# Main.net
KiCad netlist of a schematic drawn in Altium Designer
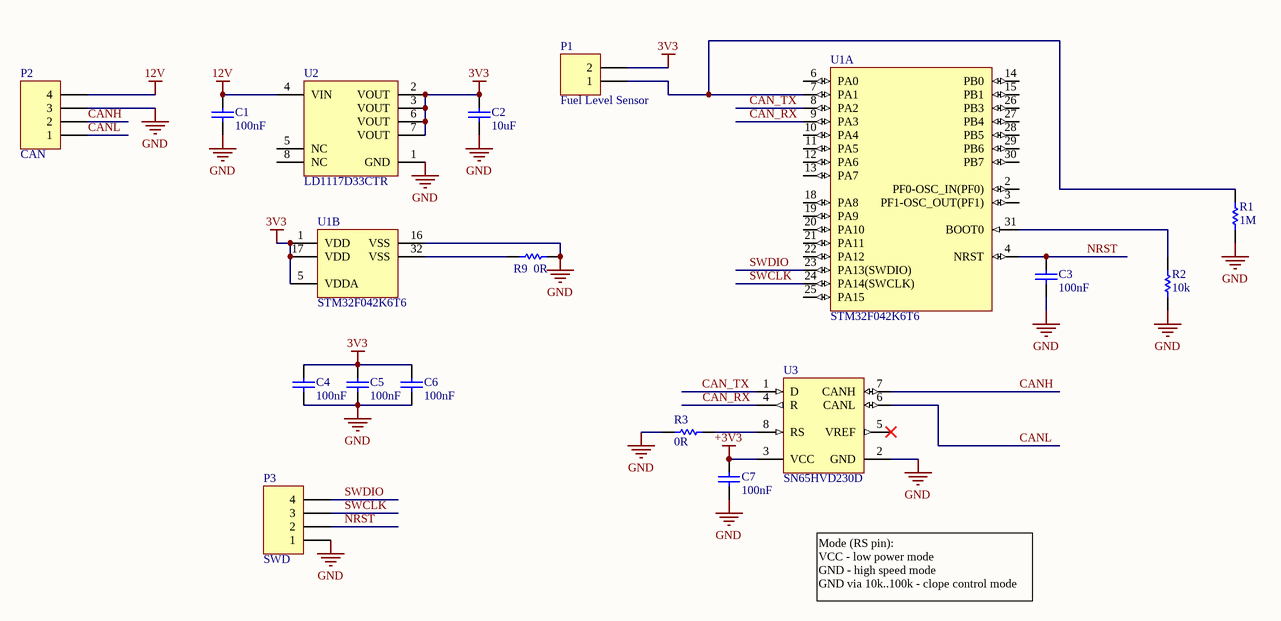
[diagram p0: Main.SchDoc]

(export (version "E")
  (design (tool "Eeschema 10.0.6"))
  (components
    (comp (ref "C1")
      (value "100nF")
      (footprint "CAP_0805_IPC_MD")
      (description "Capacitor")
      (fields (field (name "Comment") "Cap"))
      (libsource (lib "FuelLevelSensor") (part "Cap"))
    )
    (comp (ref "C2")
      (value "10uF")
      (footprint "CAP_0805_IPC_MD")
      (description "Capacitor")
      (fields (field (name "Comment") "Cap"))
      (libsource (lib "FuelLevelSensor") (part "Cap"))
    )
    (comp (ref "C3")
      (value "100nF")
      (footprint "CAP_0805_IPC_MD")
      (description "Capacitor")
      (fields (field (name "Comment") "Cap"))
      (libsource (lib "FuelLevelSensor") (part "Cap"))
    )
    (comp (ref "C4")
      (value "100nF")
      (footprint "CAP_0805_IPC_MD")
      (description "Capacitor")
      (fields (field (name "Comment") "Cap"))
      (libsource (lib "FuelLevelSensor") (part "Cap"))
    )
    (comp (ref "C5")
      (value "100nF")
      (footprint "CAP_0805_IPC_MD")
      (description "Capacitor")
      (fields (field (name "Comment") "Cap"))
      (libsource (lib "FuelLevelSensor") (part "Cap"))
    )
    (comp (ref "C6")
      (value "100nF")
      (footprint "CAP_0805_IPC_MD")
      (description "Capacitor")
      (fields (field (name "Comment") "Cap"))
      (libsource (lib "FuelLevelSensor") (part "Cap"))
    )
    (comp (ref "C7")
      (value "100nF")
      (footprint "CAP_0805_IPC_MD")
      (description "Capacitor")
      (fields (field (name "MANUFACTURER") "Samsung") (field (name "Comment") "Cap"))
      (libsource (lib "DataLogger") (part "Cap"))
    )
    (comp (ref "P1")
      (value "Fuel Level Sensor")
      (footprint "HDR1X2")
      (description "Header, 2-Pin")
      (libsource (lib "FuelLevelSensor") (part "Header 2"))
    )
    (comp (ref "P2")
      (value "CAN")
      (footprint "HDR1X4")
      (description "Header, 4-Pin")
      (libsource (lib "FuelLevelSensor") (part "Header 4"))
    )
    (comp (ref "P3")
      (value "SWD")
      (footprint "HDR1X4")
      (description "Header, 4-Pin")
      (libsource (lib "FuelLevelSensor") (part "Header 4"))
    )
    (comp (ref "R1")
      (value "1M")
      (footprint "RES_0805_IPC_MD")
      (description "Resistor")
      (fields (field (name "Comment") "Res"))
      (libsource (lib "FuelLevelSensor") (part "Res"))
    )
    (comp (ref "R2")
      (value "10k")
      (footprint "RES_0805_IPC_MD")
      (description "Resistor")
      (fields (field (name "Comment") "Res"))
      (libsource (lib "FuelLevelSensor") (part "Res"))
    )
    (comp (ref "R3")
      (value "0R")
      (footprint "RES_0805_IPC_MD")
      (description "Resistor")
      (fields (field (name "Comment") "Res"))
      (libsource (lib "DataLogger") (part "Res"))
    )
    (comp (ref "R9")
      (value "0R")
      (footprint "RES_0805_IPC_MD")
      (description "Resistor")
      (fields (field (name "Comment") "Res"))
      (libsource (lib "DataLogger") (part "Res"))
    )
    (comp (ref "U1")
      (value "STM32F042K6T6")
      (footprint "LQFP32_IPS_MD")
      (libsource (lib "FuelLevelSensor") (part "STM32F042K6T6"))
    )
    (comp (ref "U2")
      (value "LD1117D33CTR")
      (footprint "SOIC_8_IPC_MD")
      (description "Fixed Low Drop Positive Voltage Regulator, 3.3V, 8-Pin SO, Tape and Reel")
      (libsource (lib "STMicroelectronics Power Management Linear Regulator") (part "LD1117D33CTR"))
    )
    (comp (ref "U3")
      (value "SN65HVD230D")
      (footprint "SOIC_8_IPC_MD")
      (fields (field (name "MANUFACTURER") "Texas Instruments") (field (name "PARTNUMBER") "SN65HVD230DR"))
      (libsource (lib "DataLogger") (part "SN65HVD230DR"))
    )
  )
  (nets
    (net (code "1") (name "+3V3") (class "Default")
      (node (ref "C7") (pin "2") (pinfunction "2_2") (pintype "passive"))
      (node (ref "U3") (pin "3") (pinfunction "VCC_3") (pintype "power_in"))
    )
    (net (code "2") (name "/CANH") (class "Default")
      (node (ref "P2") (pin "2") (pinfunction "2_2") (pintype "passive"))
      (node (ref "U3") (pin "7") (pinfunction "CANH_7") (pintype "bidirectional"))
    )
    (net (code "3") (name "/CANL") (class "Default")
      (node (ref "P2") (pin "1") (pinfunction "1_1") (pintype "passive"))
      (node (ref "U3") (pin "6") (pinfunction "CANL_6") (pintype "bidirectional"))
    )
    (net (code "4") (name "/CAN_RX") (class "Default")
      (node (ref "U1") (pin "9") (pinfunction "PA3_9") (pintype "bidirectional"))
      (node (ref "U3") (pin "4") (pinfunction "R_4") (pintype "output"))
    )
    (net (code "5") (name "/CAN_TX") (class "Default")
      (node (ref "U1") (pin "8") (pinfunction "PA2_8") (pintype "bidirectional"))
      (node (ref "U3") (pin "1") (pinfunction "D_1") (pintype "input"))
    )
    (net (code "6") (name "/NRST") (class "Default")
      (node (ref "C3") (pin "2") (pinfunction "2_2") (pintype "passive"))
      (node (ref "P3") (pin "2") (pinfunction "2_2") (pintype "passive"))
      (node (ref "U1") (pin "4") (pinfunction "NRST_4") (pintype "bidirectional"))
    )
    (net (code "7") (name "/SWCLK") (class "Default")
      (node (ref "P3") (pin "3") (pinfunction "3_3") (pintype "passive"))
      (node (ref "U1") (pin "24") (pinfunction "PA14(SWCLK)_24") (pintype "bidirectional"))
    )
    (net (code "8") (name "/SWDIO") (class "Default")
      (node (ref "P3") (pin "4") (pinfunction "4_4") (pintype "passive"))
      (node (ref "U1") (pin "23") (pinfunction "PA13(SWDIO)_23") (pintype "bidirectional"))
    )
    (net (code "9") (name "3V3") (class "Default")
      (node (ref "C2") (pin "2") (pinfunction "2_2") (pintype "passive"))
      (node (ref "C4") (pin "2") (pinfunction "2_2") (pintype "passive"))
      (node (ref "C5") (pin "2") (pinfunction "2_2") (pintype "passive"))
      (node (ref "C6") (pin "2") (pinfunction "2_2") (pintype "passive"))
      (node (ref "P1") (pin "2") (pinfunction "2_2") (pintype "passive"))
      (node (ref "U1") (pin "1") (pinfunction "VDD_1") (pintype "power_in"))
      (node (ref "U1") (pin "17") (pinfunction "VDD_17") (pintype "power_in"))
      (node (ref "U1") (pin "5") (pinfunction "VDDA_5") (pintype "power_in"))
      (node (ref "U2") (pin "2") (pinfunction "VOUT_2") (pintype "power_in"))
      (node (ref "U2") (pin "3") (pinfunction "VOUT_3") (pintype "power_in"))
      (node (ref "U2") (pin "6") (pinfunction "VOUT_6") (pintype "power_in"))
      (node (ref "U2") (pin "7") (pinfunction "VOUT_7") (pintype "power_in"))
    )
    (net (code "10") (name "12V") (class "Default")
      (node (ref "C1") (pin "2") (pinfunction "2_2") (pintype "passive"))
      (node (ref "P2") (pin "4") (pinfunction "4_4") (pintype "passive"))
      (node (ref "U2") (pin "4") (pinfunction "VIN_4") (pintype "power_in"))
    )
    (net (code "11") (name "GND") (class "Default")
      (node (ref "C1") (pin "1") (pinfunction "1_1") (pintype "passive"))
      (node (ref "C2") (pin "1") (pinfunction "1_1") (pintype "passive"))
      (node (ref "C3") (pin "1") (pinfunction "1_1") (pintype "passive"))
      (node (ref "C4") (pin "1") (pinfunction "1_1") (pintype "passive"))
      (node (ref "C5") (pin "1") (pinfunction "1_1") (pintype "passive"))
      (node (ref "C6") (pin "1") (pinfunction "1_1") (pintype "passive"))
      (node (ref "C7") (pin "1") (pinfunction "1_1") (pintype "passive"))
      (node (ref "P2") (pin "3") (pinfunction "3_3") (pintype "passive"))
      (node (ref "P3") (pin "1") (pinfunction "1_1") (pintype "passive"))
      (node (ref "R1") (pin "1") (pinfunction "1_1") (pintype "passive"))
      (node (ref "R2") (pin "1") (pinfunction "1_1") (pintype "passive"))
      (node (ref "R3") (pin "1") (pinfunction "1_1") (pintype "passive"))
      (node (ref "R9") (pin "2") (pinfunction "2_2") (pintype "passive"))
      (node (ref "U1") (pin "16") (pinfunction "VSS_16") (pintype "power_in"))
      (node (ref "U2") (pin "1") (pinfunction "GND_1") (pintype "power_in"))
      (node (ref "U3") (pin "2") (pinfunction "GND_2") (pintype "power_in"))
    )
    (net (code "12") (name "Net-(R9-Pad1)") (class "Default")
      (node (ref "R9") (pin "1") (pinfunction "1_1") (pintype "passive"))
      (node (ref "U1") (pin "32") (pinfunction "VSS_32") (pintype "power_in"))
    )
    (net (code "13") (name "Net-(U1A-BOOT0)") (class "Default")
      (node (ref "R2") (pin "2") (pinfunction "2_2") (pintype "passive"))
      (node (ref "U1") (pin "31") (pinfunction "BOOT0_31") (pintype "input"))
    )
    (net (code "14") (name "Net-(U1A-PA1)") (class "Default")
      (node (ref "P1") (pin "1") (pinfunction "1_1") (pintype "passive"))
      (node (ref "R1") (pin "2") (pinfunction "2_2") (pintype "passive"))
      (node (ref "U1") (pin "7") (pinfunction "PA1_7") (pintype "bidirectional"))
    )
    (net (code "15") (name "Net-(U3-RS)") (class "Default")
      (node (ref "R3") (pin "2") (pinfunction "2_2") (pintype "passive"))
      (node (ref "U3") (pin "8") (pinfunction "RS_8") (pintype "input"))
    )
    (net (code "16") (name "unconnected-(U1A-PA0-Pad6)") (class "Default")
      (node (ref "U1") (pin "6") (pinfunction "PA0_6") (pintype "bidirectional"))
    )
    (net (code "17") (name "unconnected-(U1A-PA4-Pad10)") (class "Default")
      (node (ref "U1") (pin "10") (pinfunction "PA4_10") (pintype "bidirectional"))
    )
    (net (code "18") (name "unconnected-(U1A-PA5-Pad11)") (class "Default")
      (node (ref "U1") (pin "11") (pinfunction "PA5_11") (pintype "bidirectional"))
    )
    (net (code "19") (name "unconnected-(U1A-PA6-Pad12)") (class "Default")
      (node (ref "U1") (pin "12") (pinfunction "PA6_12") (pintype "bidirectional"))
    )
    (net (code "20") (name "unconnected-(U1A-PA7-Pad13)") (class "Default")
      (node (ref "U1") (pin "13") (pinfunction "PA7_13") (pintype "bidirectional"))
    )
    (net (code "21") (name "unconnected-(U1A-PA8-Pad18)") (class "Default")
      (node (ref "U1") (pin "18") (pinfunction "PA8_18") (pintype "bidirectional"))
    )
    (net (code "22") (name "unconnected-(U1A-PA9-Pad19)") (class "Default")
      (node (ref "U1") (pin "19") (pinfunction "PA9_19") (pintype "bidirectional"))
    )
    (net (code "23") (name "unconnected-(U1A-PA10-Pad20)") (class "Default")
      (node (ref "U1") (pin "20") (pinfunction "PA10_20") (pintype "bidirectional"))
    )
    (net (code "24") (name "unconnected-(U1A-PA11-Pad21)") (class "Default")
      (node (ref "U1") (pin "21") (pinfunction "PA11_21") (pintype "bidirectional"))
    )
    (net (code "25") (name "unconnected-(U1A-PA12-Pad22)") (class "Default")
      (node (ref "U1") (pin "22") (pinfunction "PA12_22") (pintype "bidirectional"))
    )
    (net (code "26") (name "unconnected-(U1A-PA15-Pad25)") (class "Default")
      (node (ref "U1") (pin "25") (pinfunction "PA15_25") (pintype "bidirectional"))
    )
    (net (code "27") (name "unconnected-(U1A-PB0-Pad14)") (class "Default")
      (node (ref "U1") (pin "14") (pinfunction "PB0_14") (pintype "bidirectional"))
    )
    (net (code "28") (name "unconnected-(U1A-PB1-Pad15)") (class "Default")
      (node (ref "U1") (pin "15") (pinfunction "PB1_15") (pintype "bidirectional"))
    )
    (net (code "29") (name "unconnected-(U1A-PB3-Pad26)") (class "Default")
      (node (ref "U1") (pin "26") (pinfunction "PB3_26") (pintype "bidirectional"))
    )
    (net (code "30") (name "unconnected-(U1A-PB4-Pad27)") (class "Default")
      (node (ref "U1") (pin "27") (pinfunction "PB4_27") (pintype "bidirectional"))
    )
    (net (code "31") (name "unconnected-(U1A-PB5-Pad28)") (class "Default")
      (node (ref "U1") (pin "28") (pinfunction "PB5_28") (pintype "bidirectional"))
    )
    (net (code "32") (name "unconnected-(U1A-PB6-Pad29)") (class "Default")
      (node (ref "U1") (pin "29") (pinfunction "PB6_29") (pintype "bidirectional"))
    )
    (net (code "33") (name "unconnected-(U1A-PB7-Pad30)") (class "Default")
      (node (ref "U1") (pin "30") (pinfunction "PB7_30") (pintype "bidirectional"))
    )
    (net (code "34") (name "unconnected-(U1A-PF0-OSC_IN(PF0)-Pad2)") (class "Default")
      (node (ref "U1") (pin "2") (pinfunction "PF0-OSC_IN(PF0)_2") (pintype "bidirectional"))
    )
    (net (code "35") (name "unconnected-(U1A-PF1-OSC_OUT(PF1)-Pad3)") (class "Default")
      (node (ref "U1") (pin "3") (pinfunction "PF1-OSC_OUT(PF1)_3") (pintype "bidirectional"))
    )
    (net (code "36") (name "unconnected-(U2-NC-Pad5)") (class "Default")
      (node (ref "U2") (pin "5") (pinfunction "NC_5") (pintype "passive"))
    )
    (net (code "37") (name "unconnected-(U2-NC-Pad8)") (class "Default")
      (node (ref "U2") (pin "8") (pinfunction "NC_8") (pintype "passive"))
    )
    (net (code "38") (name "unconnected-(U3-VREF-Pad5)") (class "Default")
      (node (ref "U3") (pin "5") (pinfunction "VREF_5") (pintype "output+no_connect"))
    )
  )
)
